# tempDonut.net
KiCad netlist of a schematic drawn in Altium Designer
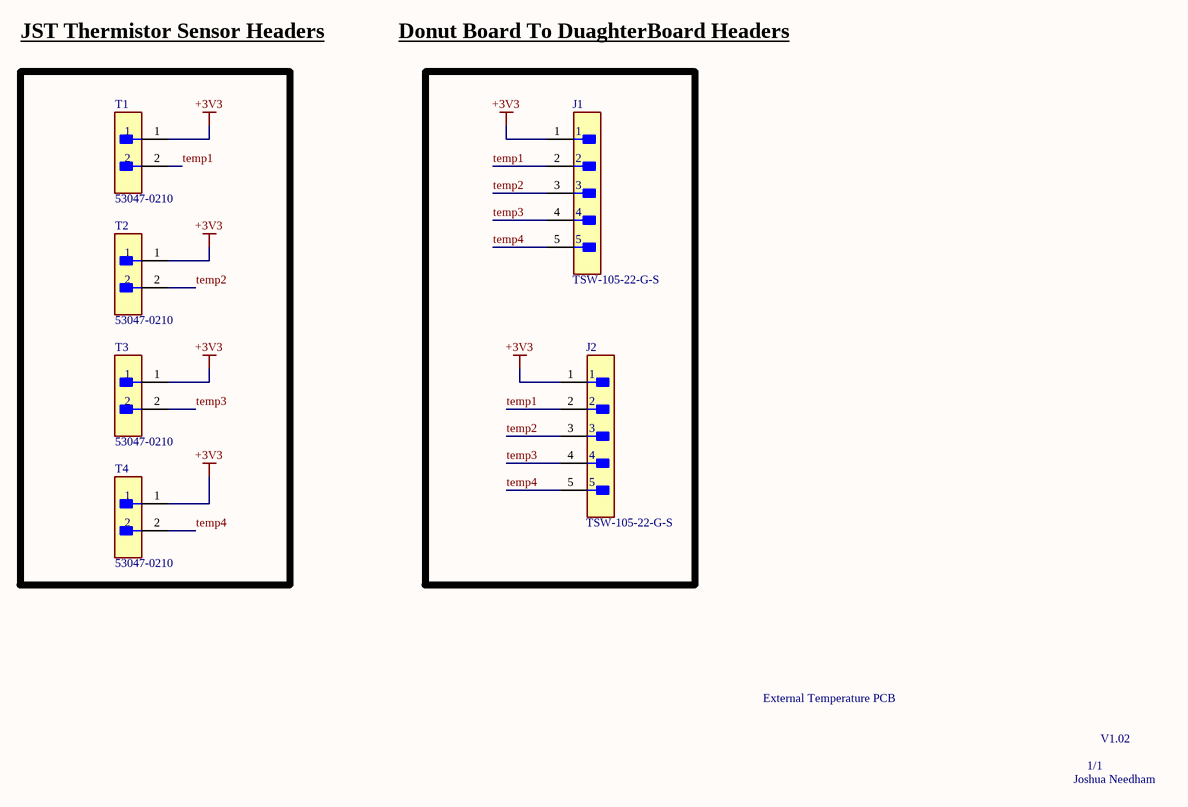
[diagram p0: tempDonut.SchDoc]

(export (version "E")
  (design (tool "Eeschema 10.0.6"))
  (components
    (comp (ref "J1")
      (value "TSW-105-22-G-S")
      (footprint "FP-TSW-105-22-G-S-MFG")
      (description "CONN HEADER VERT 5POS 2.54MM")
      (libsource (lib "Altium Content Vault") (part "bf93c07fd2649a848d0ec8585582aab"))
    )
    (comp (ref "J2")
      (value "TSW-105-22-G-S")
      (footprint "FP-TSW-105-22-G-S-MFG")
      (description "CONN HEADER VERT 5POS 2.54MM")
      (libsource (lib "Altium Content Vault") (part "bf93c07fd2649a848d0ec8585582aab"))
    )
    (comp (ref "T1")
      (value "53047-0210")
      (footprint "FP-53047-0210-MFG")
      (description "CONN HEADER VERT 2POS 1.25MM")
      (fields
        (field (name "OCTOPART") "https://octopart.com/53047-0210-molex-276772")
        (field (name "MANUFACTURER") "Molex")
      )
      (libsource (lib "Altium Content Vault") (part "3bc925449376181038e59eaffc5286c"))
    )
    (comp (ref "T2")
      (value "53047-0210")
      (footprint "FP-53047-0210-MFG")
      (description "CONN HEADER VERT 2POS 1.25MM")
      (fields
        (field (name "OCTOPART") "https://octopart.com/53047-0210-molex-276772")
        (field (name "MANUFACTURER") "Molex")
      )
      (libsource (lib "Altium Content Vault") (part "3bc925449376181038e59eaffc5286c"))
    )
    (comp (ref "T3")
      (value "53047-0210")
      (footprint "FP-53047-0210-MFG")
      (description "CONN HEADER VERT 2POS 1.25MM")
      (fields
        (field (name "OCTOPART") "https://octopart.com/53047-0210-molex-276772")
        (field (name "MANUFACTURER") "Molex")
      )
      (libsource (lib "Altium Content Vault") (part "3bc925449376181038e59eaffc5286c"))
    )
    (comp (ref "T4")
      (value "53047-0210")
      (footprint "FP-53047-0210-MFG")
      (description "CONN HEADER VERT 2POS 1.25MM")
      (fields
        (field (name "OCTOPART") "https://octopart.com/53047-0210-molex-276772")
        (field (name "MANUFACTURER") "Molex")
      )
      (libsource (lib "Altium Content Vault") (part "3bc925449376181038e59eaffc5286c"))
    )
  )
  (nets
    (net (code "1") (name "+3V3") (class "Default")
      (node (ref "J1") (pin "1") (pinfunction "1_1") (pintype "passive"))
      (node (ref "J2") (pin "1") (pinfunction "1_1") (pintype "passive"))
      (node (ref "T1") (pin "1") (pinfunction "1_1") (pintype "passive"))
      (node (ref "T2") (pin "1") (pinfunction "1_1") (pintype "passive"))
      (node (ref "T3") (pin "1") (pinfunction "1_1") (pintype "passive"))
      (node (ref "T4") (pin "1") (pinfunction "1_1") (pintype "passive"))
    )
    (net (code "2") (name "/temp1") (class "Default")
      (node (ref "J1") (pin "2") (pinfunction "2_2") (pintype "passive"))
      (node (ref "J2") (pin "2") (pinfunction "2_2") (pintype "passive"))
      (node (ref "T1") (pin "2") (pinfunction "2_2") (pintype "passive"))
    )
    (net (code "3") (name "/temp2") (class "Default")
      (node (ref "J1") (pin "3") (pinfunction "3_3") (pintype "passive"))
      (node (ref "J2") (pin "3") (pinfunction "3_3") (pintype "passive"))
      (node (ref "T2") (pin "2") (pinfunction "2_2") (pintype "passive"))
    )
    (net (code "4") (name "/temp3") (class "Default")
      (node (ref "J1") (pin "4") (pinfunction "4_4") (pintype "passive"))
      (node (ref "J2") (pin "4") (pinfunction "4_4") (pintype "passive"))
      (node (ref "T3") (pin "2") (pinfunction "2_2") (pintype "passive"))
    )
    (net (code "5") (name "/temp4") (class "Default")
      (node (ref "J1") (pin "5") (pinfunction "5_5") (pintype "passive"))
      (node (ref "J2") (pin "5") (pinfunction "5_5") (pintype "passive"))
      (node (ref "T4") (pin "2") (pinfunction "2_2") (pintype "passive"))
    )
  )
)
